# hydrogen_sensors_board_v2.net
KiCad netlist of a schematic drawn in EAGLE
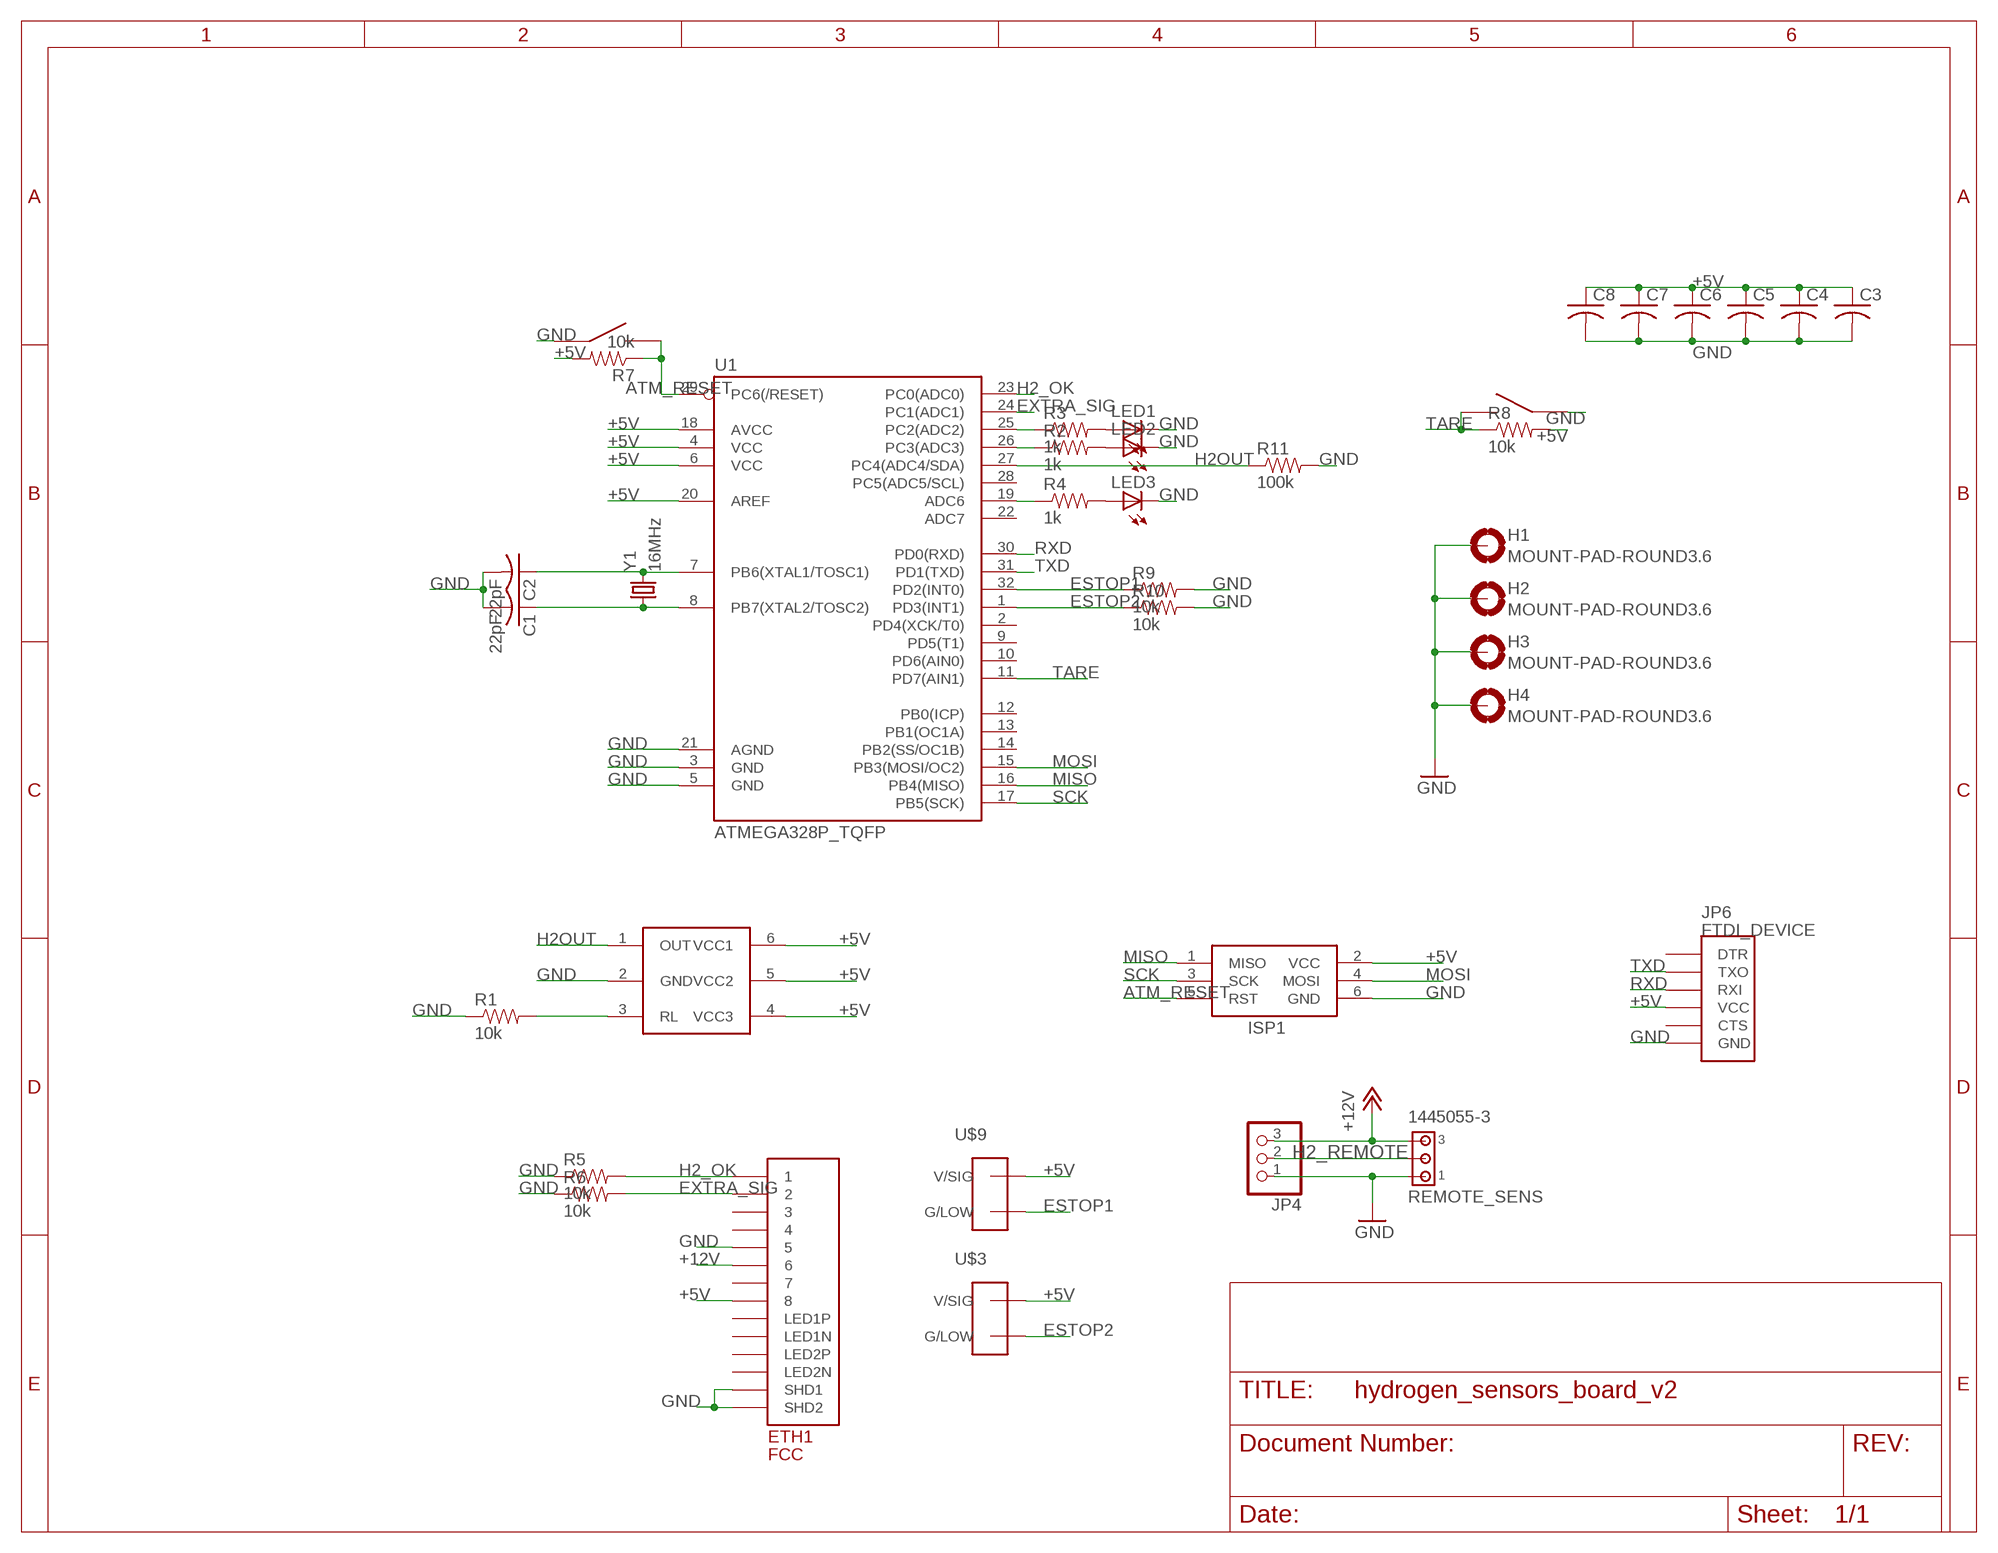
[diagram p0: schematic, sheet 1]

(export (version "E")
  (design (tool "Eeschema 10.0.6"))
  (components
    (comp (ref "C1")
      (value "22pF")
      (footprint "eagle-import:C0603K")
      (libsource (lib "eagle-import") (part "C-USC0603K"))
    )
    (comp (ref "C2")
      (value "22pF")
      (footprint "eagle-import:C0603K")
      (libsource (lib "eagle-import") (part "C-USC0603K"))
    )
    (comp (ref "C3")
      (value "C-USC0603")
      (footprint "eagle-import:C0603")
      (libsource (lib "eagle-import") (part "C-USC0603"))
    )
    (comp (ref "C4")
      (value "C-USC0603")
      (footprint "eagle-import:C0603")
      (libsource (lib "eagle-import") (part "C-USC0603"))
    )
    (comp (ref "C5")
      (value "C-USC0603")
      (footprint "eagle-import:C0603")
      (libsource (lib "eagle-import") (part "C-USC0603"))
    )
    (comp (ref "C6")
      (value "C-USC0603")
      (footprint "eagle-import:C0603")
      (libsource (lib "eagle-import") (part "C-USC0603"))
    )
    (comp (ref "C7")
      (value "C-USC0603")
      (footprint "eagle-import:C0603")
      (libsource (lib "eagle-import") (part "C-USC0603"))
    )
    (comp (ref "C8")
      (value "C-USC0603")
      (footprint "eagle-import:C0603")
      (libsource (lib "eagle-import") (part "C-USC0603"))
    )
    (comp (ref "ETH1")
      (value "FCC")
      (footprint "eagle-import:A122645-ND")
      (libsource (lib "eagle-import") (part "ETHERNET"))
    )
    (comp (ref "H1")
      (value "MOUNT-PAD-ROUND3.6")
      (footprint "eagle-import:3,6-PAD")
      (libsource (lib "eagle-import") (part "MOUNT-PAD-ROUND3.6"))
    )
    (comp (ref "H2")
      (value "MOUNT-PAD-ROUND3.6")
      (footprint "eagle-import:3,6-PAD")
      (libsource (lib "eagle-import") (part "MOUNT-PAD-ROUND3.6"))
    )
    (comp (ref "H3")
      (value "MOUNT-PAD-ROUND3.6")
      (footprint "eagle-import:3,6-PAD")
      (libsource (lib "eagle-import") (part "MOUNT-PAD-ROUND3.6"))
    )
    (comp (ref "H4")
      (value "MOUNT-PAD-ROUND3.6")
      (footprint "eagle-import:3,6-PAD")
      (libsource (lib "eagle-import") (part "MOUNT-PAD-ROUND3.6"))
    )
    (comp (ref "ISP1")
      (value "AVRISP-BOX")
      (footprint "eagle-import:AVRISP-BOX")
      (libsource (lib "eagle-import") (part "AVRISP-BOX"))
    )
    (comp (ref "JP4")
      (value "PINHD-1X3")
      (footprint "eagle-import:1X03")
      (libsource (lib "eagle-import") (part "PINHD-1X3"))
    )
    (comp (ref "JP6")
      (value "FTDI_DEVICE")
      (footprint "eagle-import:FTDI_DEVICE_SIDE")
      (libsource (lib "eagle-import") (part "FTDI_DEVICE"))
    )
    (comp (ref "LED1")
      (value "LEDCHIPLED_0805")
      (footprint "eagle-import:CHIPLED_0805")
      (libsource (lib "eagle-import") (part "LEDCHIPLED_0805"))
    )
    (comp (ref "LED2")
      (value "LEDCHIPLED_0805")
      (footprint "eagle-import:CHIPLED_0805")
      (libsource (lib "eagle-import") (part "LEDCHIPLED_0805"))
    )
    (comp (ref "LED3")
      (value "LEDCHIPLED_0805")
      (footprint "eagle-import:CHIPLED_0805")
      (libsource (lib "eagle-import") (part "LEDCHIPLED_0805"))
    )
    (comp (ref "R1")
      (value "10k")
      (footprint "eagle-import:0603-RES")
      (libsource (lib "eagle-import") (part "RESISTOR0603-RES"))
    )
    (comp (ref "R2")
      (value "1k")
      (footprint "eagle-import:0603-RES")
      (libsource (lib "eagle-import") (part "SparkFun-Resistors_RESISTOR0603-RES"))
    )
    (comp (ref "R3")
      (value "1k")
      (footprint "eagle-import:0603-RES")
      (libsource (lib "eagle-import") (part "SparkFun-Resistors_RESISTOR0603-RES"))
    )
    (comp (ref "R4")
      (value "1k")
      (footprint "eagle-import:0603-RES")
      (libsource (lib "eagle-import") (part "SparkFun-Resistors_RESISTOR0603-RES"))
    )
    (comp (ref "R5")
      (value "10k")
      (footprint "eagle-import:0603-RES")
      (libsource (lib "eagle-import") (part "RESISTOR0603-RES"))
    )
    (comp (ref "R6")
      (value "10k")
      (footprint "eagle-import:0603-RES")
      (libsource (lib "eagle-import") (part "RESISTOR0603-RES"))
    )
    (comp (ref "R7")
      (value "10k")
      (footprint "eagle-import:0603-RES")
      (libsource (lib "eagle-import") (part "SparkFun-Resistors_RESISTOR0603-RES"))
    )
    (comp (ref "R8")
      (value "10k")
      (footprint "eagle-import:0603-RES")
      (libsource (lib "eagle-import") (part "SparkFun-Resistors_RESISTOR0603-RES"))
    )
    (comp (ref "R9")
      (value "10k")
      (footprint "eagle-import:0603-RES")
      (libsource (lib "eagle-import") (part "RESISTOR0603-RES"))
    )
    (comp (ref "R10")
      (value "10k")
      (footprint "eagle-import:0603-RES")
      (libsource (lib "eagle-import") (part "RESISTOR0603-RES"))
    )
    (comp (ref "R11")
      (value "100k")
      (footprint "eagle-import:0603-RES")
      (libsource (lib "eagle-import") (part "SparkFun-Resistors_RESISTOR0603-RES"))
    )
    (comp (ref "REMOTE_SENS")
      (value "1445055-3")
      (footprint "eagle-import:1445055-3")
      (libsource (lib "eagle-import") (part "1445055-3"))
    )
    (comp (ref "U$1")
      (value "MQ-8MQ-8")
      (footprint "eagle-import:MQ-8")
      (libsource (lib "eagle-import") (part "MQ-8MQ-8"))
    )
    (comp (ref "U$2")
      (value "EG4621CT-ND")
      (footprint "eagle-import:EG4621CT-ND")
      (libsource (lib "eagle-import") (part "EG4621CT-ND"))
    )
    (comp (ref "U$3")
      (value "TE770966")
      (footprint "eagle-import:2X1-MATE-N-LOCK")
      (libsource (lib "eagle-import") (part "TE770966"))
    )
    (comp (ref "U$9")
      (value "TE770966")
      (footprint "eagle-import:2X1-MATE-N-LOCK")
      (libsource (lib "eagle-import") (part "TE770966"))
    )
    (comp (ref "U$10")
      (value "EG4621CT-ND")
      (footprint "eagle-import:EG4621CT-ND")
      (libsource (lib "eagle-import") (part "EG4621CT-ND"))
    )
    (comp (ref "U1")
      (value "ATMEGA328P_TQFP")
      (footprint "eagle-import:TQFP32-08")
      (libsource (lib "eagle-import") (part "ATMEGA328P_TQFP"))
    )
    (comp (ref "Y1")
      (value "16MHz")
      (footprint "eagle-import:HC49US")
      (libsource (lib "eagle-import") (part "CRYSTALHC49US"))
    )
  )
  (nets
    (net (code "1") (name "+12V") (class "Default")
      (node (ref "ETH1") (pin "P$6") (pinfunction "6_P$6") (pintype "bidirectional"))
      (node (ref "JP4") (pin "3") (pinfunction "3_3") (pintype "passive"))
      (node (ref "REMOTE_SENS") (pin "3") (pinfunction "3_3") (pintype "passive"))
    )
    (net (code "2") (name "/+5V") (class "Default")
      (node (ref "C3") (pin "1") (pinfunction "1_1") (pintype "passive"))
      (node (ref "C4") (pin "1") (pinfunction "1_1") (pintype "passive"))
      (node (ref "C5") (pin "1") (pinfunction "1_1") (pintype "passive"))
      (node (ref "C6") (pin "1") (pinfunction "1_1") (pintype "passive"))
      (node (ref "C7") (pin "1") (pinfunction "1_1") (pintype "passive"))
      (node (ref "C8") (pin "1") (pinfunction "1_1") (pintype "passive"))
      (node (ref "ETH1") (pin "P$8") (pinfunction "8_P$8") (pintype "bidirectional"))
      (node (ref "ISP1") (pin "2") (pinfunction "VCC_2") (pintype "power_in"))
      (node (ref "JP6") (pin "P$4") (pinfunction "VCC_P$4") (pintype "bidirectional"))
      (node (ref "R7") (pin "2") (pinfunction "2_2") (pintype "passive"))
      (node (ref "R8") (pin "2") (pinfunction "2_2") (pintype "passive"))
      (node (ref "U$1") (pin "4") (pinfunction "VCC3_4") (pintype "bidirectional"))
      (node (ref "U$1") (pin "5") (pinfunction "VCC2_5") (pintype "bidirectional"))
      (node (ref "U$1") (pin "6") (pinfunction "VCC1_6") (pintype "bidirectional"))
      (node (ref "U$3") (pin "CIRCUIT1") (pinfunction "V/SIG_CIRCUIT1") (pintype "bidirectional"))
      (node (ref "U$9") (pin "CIRCUIT1") (pinfunction "V/SIG_CIRCUIT1") (pintype "bidirectional"))
      (node (ref "U1") (pin "18") (pinfunction "AVCC_18") (pintype "bidirectional"))
      (node (ref "U1") (pin "20") (pinfunction "AREF_20") (pintype "bidirectional"))
      (node (ref "U1") (pin "4") (pinfunction "VCC_4") (pintype "bidirectional"))
      (node (ref "U1") (pin "6") (pinfunction "VCC_6") (pintype "bidirectional"))
    )
    (net (code "3") (name "/ATM_RESET") (class "Default")
      (node (ref "ISP1") (pin "5") (pinfunction "RST_5") (pintype "output"))
      (node (ref "R7") (pin "1") (pinfunction "1_1") (pintype "passive"))
      (node (ref "U$10") (pin "P$3") (pinfunction "P$2_P$3") (pintype "bidirectional"))
      (node (ref "U$10") (pin "P$4") (pinfunction "P$2_P$4") (pintype "bidirectional"))
      (node (ref "U1") (pin "29") (pinfunction "PC6(/RESET)_29") (pintype "bidirectional"))
    )
    (net (code "4") (name "/ESTOP1") (class "Default")
      (node (ref "R9") (pin "1") (pinfunction "1_1") (pintype "passive"))
      (node (ref "U$9") (pin "CIRCUIT2") (pinfunction "G/LOW_CIRCUIT2") (pintype "bidirectional"))
      (node (ref "U1") (pin "32") (pinfunction "PD2(INT0)_32") (pintype "bidirectional"))
    )
    (net (code "5") (name "/ESTOP2") (class "Default")
      (node (ref "R10") (pin "1") (pinfunction "1_1") (pintype "passive"))
      (node (ref "U$3") (pin "CIRCUIT2") (pinfunction "G/LOW_CIRCUIT2") (pintype "bidirectional"))
      (node (ref "U1") (pin "1") (pinfunction "PD3(INT1)_1") (pintype "bidirectional"))
    )
    (net (code "6") (name "/EXTRA_SIG") (class "Default")
      (node (ref "ETH1") (pin "P$2") (pinfunction "2_P$2") (pintype "bidirectional"))
      (node (ref "R6") (pin "2") (pinfunction "2_2") (pintype "passive"))
      (node (ref "U1") (pin "24") (pinfunction "PC1(ADC1)_24") (pintype "bidirectional"))
    )
    (net (code "7") (name "/H2OUT") (class "Default")
      (node (ref "R11") (pin "1") (pinfunction "1_1") (pintype "passive"))
      (node (ref "U$1") (pin "1") (pinfunction "OUT_1") (pintype "bidirectional"))
      (node (ref "U1") (pin "27") (pinfunction "PC4(ADC4/SDA)_27") (pintype "bidirectional"))
    )
    (net (code "8") (name "/H2_OK") (class "Default")
      (node (ref "ETH1") (pin "P$1") (pinfunction "1_P$1") (pintype "bidirectional"))
      (node (ref "R5") (pin "2") (pinfunction "2_2") (pintype "passive"))
      (node (ref "U1") (pin "23") (pinfunction "PC0(ADC0)_23") (pintype "bidirectional"))
    )
    (net (code "9") (name "/H2_REMOTE") (class "Default")
      (node (ref "JP4") (pin "2") (pinfunction "2_2") (pintype "passive"))
      (node (ref "REMOTE_SENS") (pin "2") (pinfunction "2_2") (pintype "passive"))
    )
    (net (code "10") (name "/MISO") (class "Default")
      (node (ref "ISP1") (pin "1") (pinfunction "MISO_1") (pintype "input"))
      (node (ref "U1") (pin "16") (pinfunction "PB4(MISO)_16") (pintype "bidirectional"))
    )
    (net (code "11") (name "/MOSI") (class "Default")
      (node (ref "ISP1") (pin "4") (pinfunction "MOSI_4") (pintype "output"))
      (node (ref "U1") (pin "15") (pinfunction "PB3(MOSI/OC2)_15") (pintype "bidirectional"))
    )
    (net (code "12") (name "/RXD") (class "Default")
      (node (ref "JP6") (pin "P$3") (pinfunction "RXI_P$3") (pintype "bidirectional"))
      (node (ref "U1") (pin "30") (pinfunction "PD0(RXD)_30") (pintype "bidirectional"))
    )
    (net (code "13") (name "/SCK") (class "Default")
      (node (ref "ISP1") (pin "3") (pinfunction "SCK_3") (pintype "output"))
      (node (ref "U1") (pin "17") (pinfunction "PB5(SCK)_17") (pintype "bidirectional"))
    )
    (net (code "14") (name "/TARE") (class "Default")
      (node (ref "R8") (pin "1") (pinfunction "1_1") (pintype "passive"))
      (node (ref "U$2") (pin "P$3") (pinfunction "P$2_P$3") (pintype "bidirectional"))
      (node (ref "U$2") (pin "P$4") (pinfunction "P$2_P$4") (pintype "bidirectional"))
      (node (ref "U1") (pin "11") (pinfunction "PD7(AIN1)_11") (pintype "bidirectional"))
    )
    (net (code "15") (name "/TXD") (class "Default")
      (node (ref "JP6") (pin "P$2") (pinfunction "TXO_P$2") (pintype "bidirectional"))
      (node (ref "U1") (pin "31") (pinfunction "PD1(TXD)_31") (pintype "bidirectional"))
    )
    (net (code "16") (name "GND") (class "Default")
      (node (ref "C1") (pin "2") (pinfunction "2_2") (pintype "passive"))
      (node (ref "C2") (pin "2") (pinfunction "2_2") (pintype "passive"))
      (node (ref "C3") (pin "2") (pinfunction "2_2") (pintype "passive"))
      (node (ref "C4") (pin "2") (pinfunction "2_2") (pintype "passive"))
      (node (ref "C5") (pin "2") (pinfunction "2_2") (pintype "passive"))
      (node (ref "C6") (pin "2") (pinfunction "2_2") (pintype "passive"))
      (node (ref "C7") (pin "2") (pinfunction "2_2") (pintype "passive"))
      (node (ref "C8") (pin "2") (pinfunction "2_2") (pintype "passive"))
      (node (ref "ETH1") (pin "P$13") (pinfunction "SHD1_P$13") (pintype "bidirectional"))
      (node (ref "ETH1") (pin "P$14") (pinfunction "SHD2_P$14") (pintype "bidirectional"))
      (node (ref "ETH1") (pin "P$5") (pinfunction "5_P$5") (pintype "bidirectional"))
      (node (ref "H1") (pin "B3,6") (pinfunction "MOUNT_B3,6") (pintype "passive"))
      (node (ref "H2") (pin "B3,6") (pinfunction "MOUNT_B3,6") (pintype "passive"))
      (node (ref "H3") (pin "B3,6") (pinfunction "MOUNT_B3,6") (pintype "passive"))
      (node (ref "H4") (pin "B3,6") (pinfunction "MOUNT_B3,6") (pintype "passive"))
      (node (ref "ISP1") (pin "6") (pinfunction "GND_6") (pintype "power_in"))
      (node (ref "JP4") (pin "1") (pinfunction "1_1") (pintype "passive"))
      (node (ref "JP6") (pin "P$6") (pinfunction "GND_P$6") (pintype "bidirectional"))
      (node (ref "LED1") (pin "C") (pinfunction "C_C") (pintype "passive"))
      (node (ref "LED2") (pin "C") (pinfunction "C_C") (pintype "passive"))
      (node (ref "LED3") (pin "C") (pinfunction "C_C") (pintype "passive"))
      (node (ref "R1") (pin "1") (pinfunction "1_1") (pintype "passive"))
      (node (ref "R10") (pin "2") (pinfunction "2_2") (pintype "passive"))
      (node (ref "R11") (pin "2") (pinfunction "2_2") (pintype "passive"))
      (node (ref "R5") (pin "1") (pinfunction "1_1") (pintype "passive"))
      (node (ref "R6") (pin "1") (pinfunction "1_1") (pintype "passive"))
      (node (ref "R9") (pin "2") (pinfunction "2_2") (pintype "passive"))
      (node (ref "REMOTE_SENS") (pin "1") (pinfunction "1_1") (pintype "passive"))
      (node (ref "U$1") (pin "2") (pinfunction "GND_2") (pintype "bidirectional"))
      (node (ref "U$10") (pin "P$1") (pinfunction "P$1_P$1") (pintype "bidirectional"))
      (node (ref "U$10") (pin "P$2") (pinfunction "P$1_P$2") (pintype "bidirectional"))
      (node (ref "U$2") (pin "P$1") (pinfunction "P$1_P$1") (pintype "bidirectional"))
      (node (ref "U$2") (pin "P$2") (pinfunction "P$1_P$2") (pintype "bidirectional"))
      (node (ref "U1") (pin "21") (pinfunction "AGND_21") (pintype "bidirectional"))
      (node (ref "U1") (pin "3") (pinfunction "GND_3") (pintype "bidirectional"))
      (node (ref "U1") (pin "5") (pinfunction "GND_5") (pintype "bidirectional"))
    )
    (net (code "17") (name "Net-(LED1-PadA)") (class "Default")
      (node (ref "LED1") (pin "A") (pinfunction "A_A") (pintype "passive"))
      (node (ref "R3") (pin "2") (pinfunction "2_2") (pintype "passive"))
    )
    (net (code "18") (name "Net-(LED2-PadA)") (class "Default")
      (node (ref "LED2") (pin "A") (pinfunction "A_A") (pintype "passive"))
      (node (ref "R2") (pin "2") (pinfunction "2_2") (pintype "passive"))
    )
    (net (code "19") (name "Net-(LED3-PadA)") (class "Default")
      (node (ref "LED3") (pin "A") (pinfunction "A_A") (pintype "passive"))
      (node (ref "R4") (pin "2") (pinfunction "2_2") (pintype "passive"))
    )
    (net (code "20") (name "Net-(U$1-RL)") (class "Default")
      (node (ref "R1") (pin "2") (pinfunction "2_2") (pintype "passive"))
      (node (ref "U$1") (pin "3") (pinfunction "RL_3") (pintype "bidirectional"))
    )
    (net (code "21") (name "Net-(U1-ADC6)") (class "Default")
      (node (ref "R4") (pin "1") (pinfunction "1_1") (pintype "passive"))
      (node (ref "U1") (pin "19") (pinfunction "ADC6_19") (pintype "bidirectional"))
    )
    (net (code "22") (name "Net-(U1-PB6(XTAL1{slash}TOSC1))") (class "Default")
      (node (ref "C2") (pin "1") (pinfunction "1_1") (pintype "passive"))
      (node (ref "U1") (pin "7") (pinfunction "PB6(XTAL1/TOSC1)_7") (pintype "bidirectional"))
      (node (ref "Y1") (pin "2") (pinfunction "2_2") (pintype "passive"))
    )
    (net (code "23") (name "Net-(U1-PB7(XTAL2{slash}TOSC2))") (class "Default")
      (node (ref "C1") (pin "1") (pinfunction "1_1") (pintype "passive"))
      (node (ref "U1") (pin "8") (pinfunction "PB7(XTAL2/TOSC2)_8") (pintype "bidirectional"))
      (node (ref "Y1") (pin "1") (pinfunction "1_1") (pintype "passive"))
    )
    (net (code "24") (name "Net-(U1-PC2(ADC2))") (class "Default")
      (node (ref "R3") (pin "1") (pinfunction "1_1") (pintype "passive"))
      (node (ref "U1") (pin "25") (pinfunction "PC2(ADC2)_25") (pintype "bidirectional"))
    )
    (net (code "25") (name "Net-(U1-PC3(ADC3))") (class "Default")
      (node (ref "R2") (pin "1") (pinfunction "1_1") (pintype "passive"))
      (node (ref "U1") (pin "26") (pinfunction "PC3(ADC3)_26") (pintype "bidirectional"))
    )
    (net (code "26") (name "unconnected-(ETH1-3-PadP$3)") (class "Default")
      (node (ref "ETH1") (pin "P$3") (pinfunction "3_P$3") (pintype "bidirectional"))
    )
    (net (code "27") (name "unconnected-(ETH1-4-PadP$4)") (class "Default")
      (node (ref "ETH1") (pin "P$4") (pinfunction "4_P$4") (pintype "bidirectional"))
    )
    (net (code "28") (name "unconnected-(ETH1-7-PadP$7)") (class "Default")
      (node (ref "ETH1") (pin "P$7") (pinfunction "7_P$7") (pintype "bidirectional"))
    )
    (net (code "29") (name "unconnected-(ETH1-LED1N-PadP$9)") (class "Default")
      (node (ref "ETH1") (pin "P$9") (pinfunction "LED1N_P$9") (pintype "bidirectional"))
    )
    (net (code "30") (name "unconnected-(ETH1-LED1P-PadP$10)") (class "Default")
      (node (ref "ETH1") (pin "P$10") (pinfunction "LED1P_P$10") (pintype "bidirectional"))
    )
    (net (code "31") (name "unconnected-(ETH1-LED2N-PadP$11)") (class "Default")
      (node (ref "ETH1") (pin "P$11") (pinfunction "LED2N_P$11") (pintype "bidirectional"))
    )
    (net (code "32") (name "unconnected-(ETH1-LED2P-PadP$12)") (class "Default")
      (node (ref "ETH1") (pin "P$12") (pinfunction "LED2P_P$12") (pintype "bidirectional"))
    )
    (net (code "33") (name "unconnected-(JP6-CTS-PadP$5)") (class "Default")
      (node (ref "JP6") (pin "P$5") (pinfunction "CTS_P$5") (pintype "bidirectional"))
    )
    (net (code "34") (name "unconnected-(JP6-DTR-PadP$1)") (class "Default")
      (node (ref "JP6") (pin "P$1") (pinfunction "DTR_P$1") (pintype "bidirectional"))
    )
    (net (code "35") (name "unconnected-(U1-ADC7-Pad22)") (class "Default")
      (node (ref "U1") (pin "22") (pinfunction "ADC7_22") (pintype "bidirectional"))
    )
    (net (code "36") (name "unconnected-(U1-PB0(ICP)-Pad12)") (class "Default")
      (node (ref "U1") (pin "12") (pinfunction "PB0(ICP)_12") (pintype "bidirectional"))
    )
    (net (code "37") (name "unconnected-(U1-PB1(OC1A)-Pad13)") (class "Default")
      (node (ref "U1") (pin "13") (pinfunction "PB1(OC1A)_13") (pintype "bidirectional"))
    )
    (net (code "38") (name "unconnected-(U1-PB2(SS{slash}OC1B)-Pad14)") (class "Default")
      (node (ref "U1") (pin "14") (pinfunction "PB2(SS/OC1B)_14") (pintype "bidirectional"))
    )
    (net (code "39") (name "unconnected-(U1-PC5(ADC5{slash}SCL)-Pad28)") (class "Default")
      (node (ref "U1") (pin "28") (pinfunction "PC5(ADC5/SCL)_28") (pintype "bidirectional"))
    )
    (net (code "40") (name "unconnected-(U1-PD4(XCK{slash}T0)-Pad2)") (class "Default")
      (node (ref "U1") (pin "2") (pinfunction "PD4(XCK/T0)_2") (pintype "bidirectional"))
    )
    (net (code "41") (name "unconnected-(U1-PD5(T1)-Pad9)") (class "Default")
      (node (ref "U1") (pin "9") (pinfunction "PD5(T1)_9") (pintype "bidirectional"))
    )
    (net (code "42") (name "unconnected-(U1-PD6(AIN0)-Pad10)") (class "Default")
      (node (ref "U1") (pin "10") (pinfunction "PD6(AIN0)_10") (pintype "bidirectional"))
    )
  )
)
